# Line_follower1_Sheet.net
KiCad netlist of a schematic drawn in Altium Designer
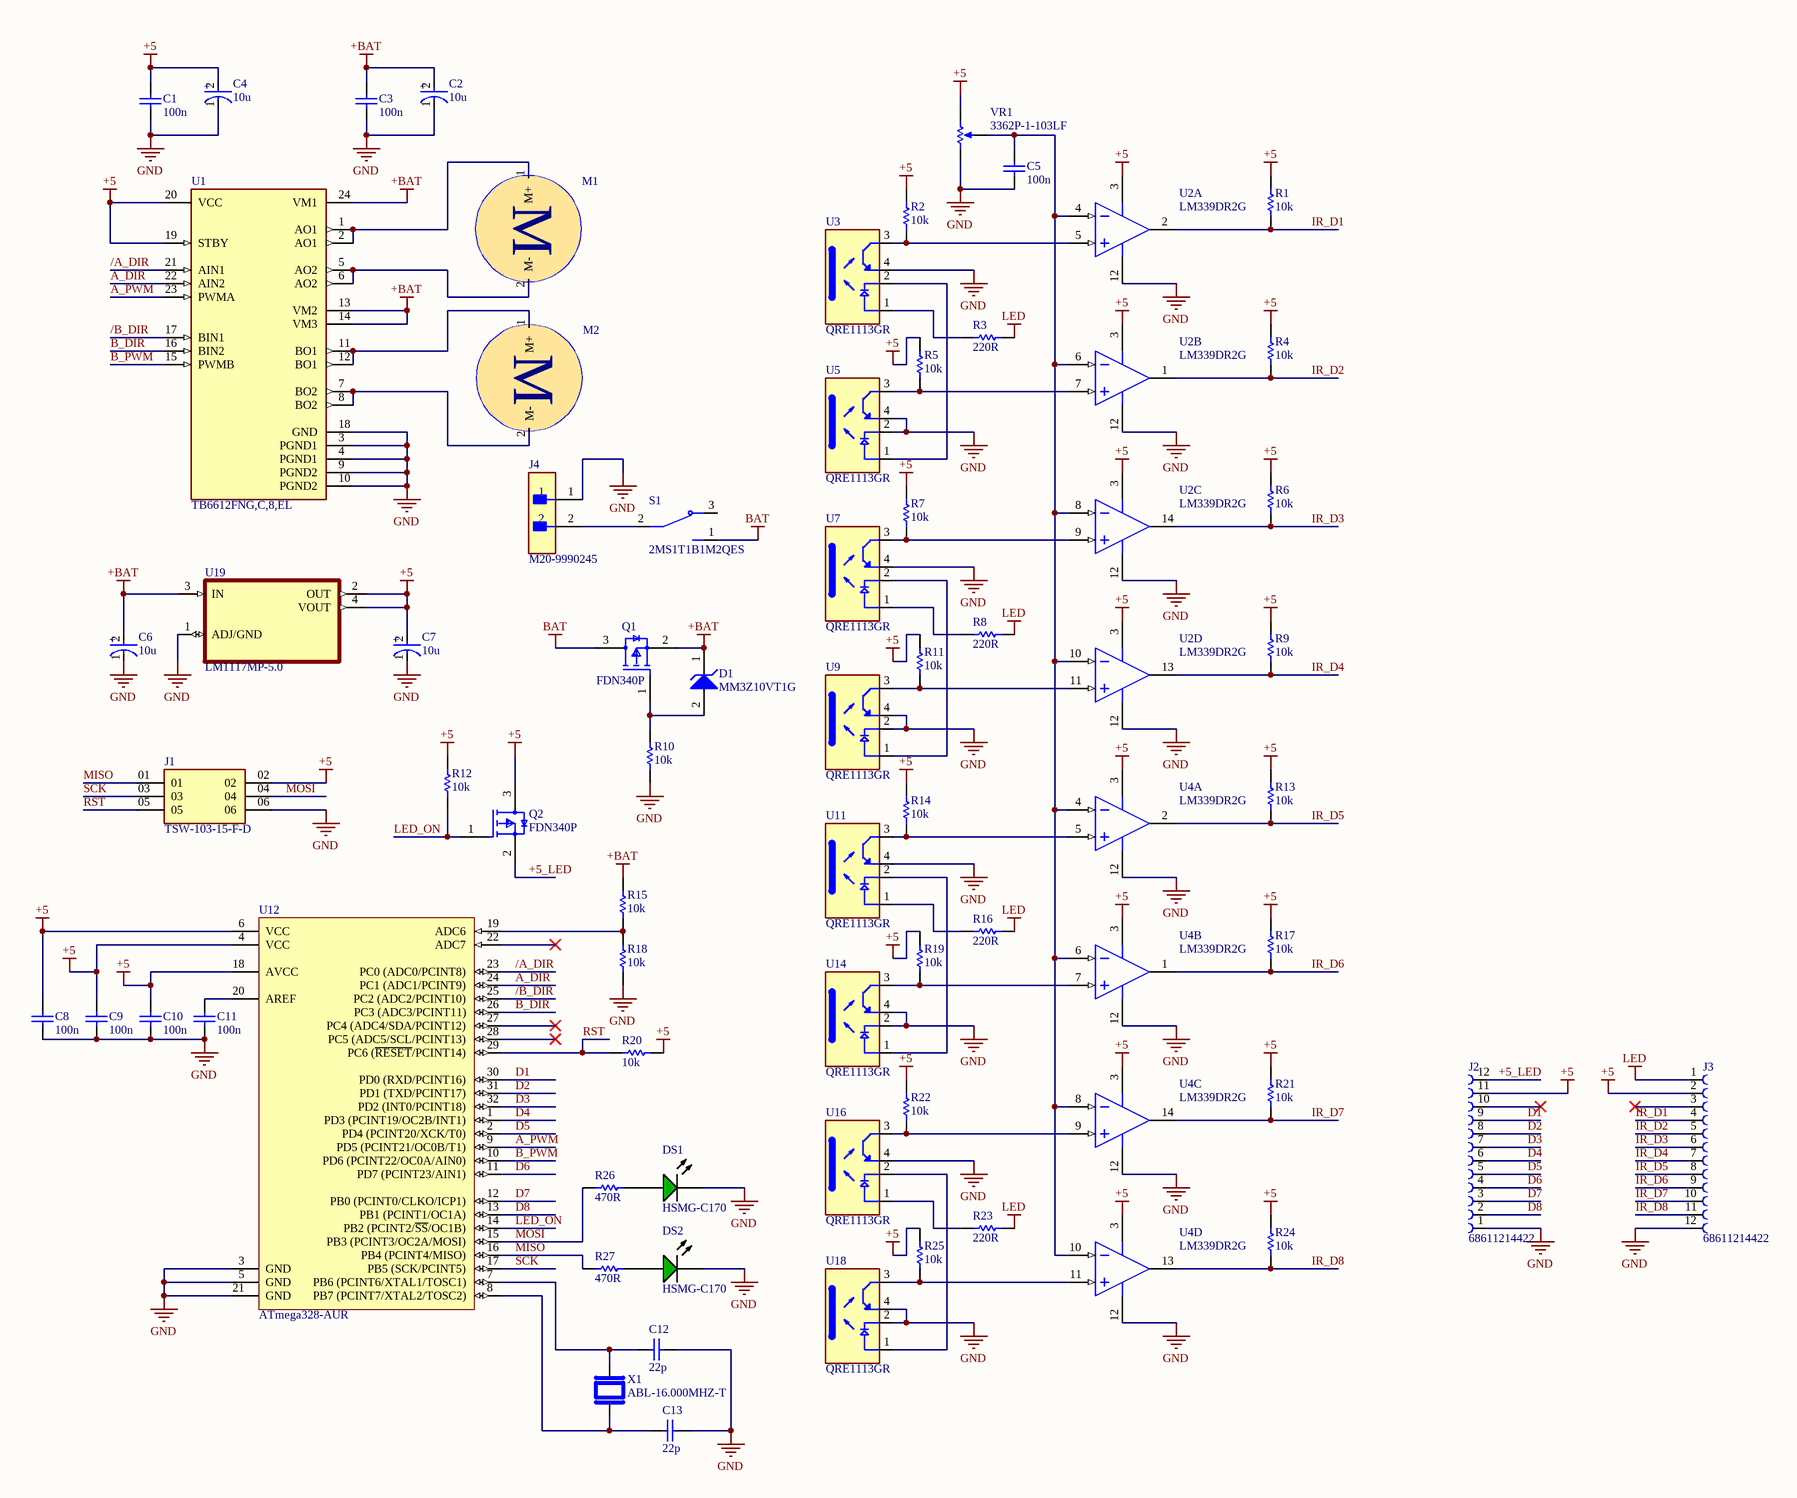
[diagram p0: Line_follower1_Sheet.SchDoc]

(export (version "E")
  (design (tool "Eeschema 10.0.6"))
  (components
    (comp (ref "C1")
      (value "100n")
      (footprint "CAPC2013X88X50LL20T25")
      (description "0805")
      (fields (field (name "MANUFACTURER") "Kemet") (field (name "PART NUMBER") "C0805C103K5RACTU"))
      (libsource (lib "Altium Content Vault") (part "CAP"))
    )
    (comp (ref "C2")
      (value "10u")
      (footprint "FP-T491B106K020AT-MFG")
      (description "CAP TANT 10UF 10% 20V 1411")
      (fields (field (name "TOLERANCE") "10%") (field (name "VOLTAGE") "20V"))
      (libsource (lib "Altium Content Vault") (part "a00bbbee19879c290e62620ae7e47b1"))
    )
    (comp (ref "C3")
      (value "100n")
      (footprint "CAPC2013X88X50LL20T25")
      (description "0805")
      (fields (field (name "MANUFACTURER") "Kemet") (field (name "PART NUMBER") "C0805C103K5RACTU"))
      (libsource (lib "Altium Content Vault") (part "CAP"))
    )
    (comp (ref "C4")
      (value "10u")
      (footprint "FP-T491B106K020AT-MFG")
      (description "CAP TANT 10UF 10% 20V 1411")
      (fields (field (name "TOLERANCE") "10%") (field (name "VOLTAGE") "20V"))
      (libsource (lib "Altium Content Vault") (part "a00bbbee19879c290e62620ae7e47b1"))
    )
    (comp (ref "C5")
      (value "100n")
      (footprint "CAPC2013X88X50LL20T25")
      (description "0805")
      (fields (field (name "MANUFACTURER") "Kemet") (field (name "PART NUMBER") "C0805C103K5RACTU"))
      (libsource (lib "Altium Content Vault") (part "CAP"))
    )
    (comp (ref "C6")
      (value "10u")
      (footprint "FP-T491B106K020AT-MFG")
      (description "CAP TANT 10UF 10% 20V 1411")
      (fields (field (name "TOLERANCE") "10%") (field (name "VOLTAGE") "20V"))
      (libsource (lib "Altium Content Vault") (part "a00bbbee19879c290e62620ae7e47b1"))
    )
    (comp (ref "C7")
      (value "10u")
      (footprint "FP-T491B106K020AT-MFG")
      (description "CAP TANT 10UF 10% 20V 1411")
      (fields (field (name "TOLERANCE") "10%") (field (name "VOLTAGE") "20V"))
      (libsource (lib "Altium Content Vault") (part "a00bbbee19879c290e62620ae7e47b1"))
    )
    (comp (ref "C8")
      (value "100n")
      (footprint "CAPC2013X88X50LL20T25")
      (description "0805")
      (fields (field (name "MANUFACTURER") "Kemet") (field (name "PART NUMBER") "C0805C103K5RACTU"))
      (libsource (lib "Altium Content Vault") (part "CAP"))
    )
    (comp (ref "C9")
      (value "100n")
      (footprint "CAPC2013X88X50LL20T25")
      (description "0805")
      (fields (field (name "MANUFACTURER") "Kemet") (field (name "PART NUMBER") "C0805C103K5RACTU"))
      (libsource (lib "Altium Content Vault") (part "CAP"))
    )
    (comp (ref "C10")
      (value "100n")
      (footprint "CAPC2013X88X50LL20T25")
      (description "0805")
      (fields (field (name "MANUFACTURER") "Kemet") (field (name "PART NUMBER") "C0805C103K5RACTU"))
      (libsource (lib "Altium Content Vault") (part "CAP"))
    )
    (comp (ref "C11")
      (value "100n")
      (footprint "CAPC2013X88X50LL20T25")
      (description "0805")
      (fields (field (name "MANUFACTURER") "Kemet") (field (name "PART NUMBER") "C0805C103K5RACTU"))
      (libsource (lib "Altium Content Vault") (part "CAP"))
    )
    (comp (ref "C12")
      (value "22p")
      (footprint "CAPC2013X88X50LL20T25")
      (description "0805")
      (fields (field (name "MANUFACTURER") "Kemet") (field (name "PART NUMBER") "C0805C103K5RACTU"))
      (libsource (lib "Altium Content Vault") (part "CAP"))
    )
    (comp (ref "C13")
      (value "22p")
      (footprint "CAPC2013X88X50LL20T25")
      (description "0805")
      (fields (field (name "MANUFACTURER") "Kemet") (field (name "PART NUMBER") "C0805C103K5RACTU"))
      (libsource (lib "Altium Content Vault") (part "CAP"))
    )
    (comp (ref "D1")
      (value "MM3Z10VT1G")
      (footprint "ONSC-SOD-323-2-477-02_V")
      (description "Zener Voltage Regulator, 300 mW, 2-Pin SOD-323, Pb-Free, Tape and Reel")
      (fields (field (name "MANUFACTURER") "On Semiconductor"))
      (libsource (lib "Altium Content Vault") (part "ONSC-K1A2-2"))
    )
    (comp (ref "DS1")
      (value "HSMG-C170")
      (footprint "AVAG-HSMX-C170_V")
      (description "Chip LED, Green, 2.2 V, -40 to 85 degC, 2-Pin SMD, Pb-Free, Tape and Reel")
      (fields (field (name "MANUFACTURER") "Avago"))
      (libsource (lib "Altium Content Vault") (part "LED_GREEN_A1K2-2"))
    )
    (comp (ref "DS2")
      (value "HSMG-C170")
      (footprint "AVAG-HSMX-C170_V")
      (description "Chip LED, Green, 2.2 V, -40 to 85 degC, 2-Pin SMD, Pb-Free, Tape and Reel")
      (fields (field (name "MANUFACTURER") "Avago"))
      (libsource (lib "Altium Content Vault") (part "LED_GREEN_A1K2-2"))
    )
    (comp (ref "J1")
      (value "TSW-103-15-F-D")
      (footprint "SAMTEC_TSW-103-15-F-D")
      (libsource (lib "TSW-103-15-F-D") (part "TSW-103-15-F-D"))
    )
    (comp (ref "J2")
      (value "68611214422")
      (footprint "68611214422")
      (description "12 Position FPC Connector Contacts, Bottom 0.039 (1.00mm) Surface Mount, Right Angle")
      (fields (field (name "MF") "Wurth Elektronik"))
      (libsource (lib "68611214422") (part "68611214422"))
    )
    (comp (ref "J3")
      (value "68611214422")
      (footprint "68611214422")
      (description "12 Position FPC Connector Contacts, Bottom 0.039 (1.00mm) Surface Mount, Right Angle")
      (fields (field (name "MF") "Wurth Elektronik"))
      (libsource (lib "68611214422") (part "68611214422"))
    )
    (comp (ref "J4")
      (value "M20-9990245")
      (footprint "FP-M20-9990245-MFG")
      (description "CONN HEADER VERT 2POS 2.54MM")
      (fields (field (name "VOLTAGE") "50V"))
      (libsource (lib "Altium Content Vault") (part "3bc925449376181038e59eaffc5286c"))
    )
    (comp (ref "M1")
      (value "Component_1")
      (footprint "PCBComponent_1")
      (description "Pady do silnika")
      (libsource (lib "PadyDoN20") (part "Component_1"))
    )
    (comp (ref "M2")
      (value "Component_1")
      (footprint "PCBComponent_1")
      (description "Pady do silnika")
      (libsource (lib "PadyDoN20") (part "Component_1"))
    )
    (comp (ref "Q1")
      (value "FDN340P")
      (footprint "FP-527AG-MFG")
      (description "MOSFET P-CH 20V 2A SSOT3")
      (libsource (lib "Altium Content Vault") (part "d23f43cc42f60b967b7caccf14518fd"))
    )
    (comp (ref "Q2")
      (value "FDN340P")
      (footprint "FP-527AG-MFG")
      (description "MOSFET P-CH 20V 2A SSOT3")
      (libsource (lib "Altium Content Vault") (part "d23f43cc42f60b967b7caccf14518fd"))
    )
    (comp (ref "R1")
      (value "10k")
      (footprint "RESC0805(2012)_L")
      (description "10K 0.125W 1% 0805 (2012 Metric)  SMD")
      (fields (field (name "TOLERANCE") "1 %") (field (name "POWER") "0.125 W"))
      (libsource (lib "Altium Content Vault") (part "RES"))
    )
    (comp (ref "R2")
      (value "10k")
      (footprint "RESC0805(2012)_L")
      (description "10K 0.125W 1% 0805 (2012 Metric)  SMD")
      (fields (field (name "TOLERANCE") "1 %") (field (name "POWER") "0.125 W"))
      (libsource (lib "Altium Content Vault") (part "RES"))
    )
    (comp (ref "R3")
      (value "220R")
      (footprint "RESC0805(2012)_L")
      (description "220 0.125W 1% 0805 (2012 Metric)  SMD")
      (fields (field (name "TOLERANCE") "1 %") (field (name "POWER") "0.125 W"))
      (libsource (lib "Altium Content Vault") (part "RES"))
    )
    (comp (ref "R4")
      (value "10k")
      (footprint "RESC0805(2012)_L")
      (description "10K 0.125W 1% 0805 (2012 Metric)  SMD")
      (fields (field (name "TOLERANCE") "1 %") (field (name "POWER") "0.125 W"))
      (libsource (lib "Altium Content Vault") (part "RES"))
    )
    (comp (ref "R5")
      (value "10k")
      (footprint "RESC0805(2012)_L")
      (description "10K 0.125W 1% 0805 (2012 Metric)  SMD")
      (fields (field (name "TOLERANCE") "1 %") (field (name "POWER") "0.125 W"))
      (libsource (lib "Altium Content Vault") (part "RES"))
    )
    (comp (ref "R6")
      (value "10k")
      (footprint "RESC0805(2012)_L")
      (description "10K 0.125W 1% 0805 (2012 Metric)  SMD")
      (fields (field (name "TOLERANCE") "1 %") (field (name "POWER") "0.125 W"))
      (libsource (lib "Altium Content Vault") (part "RES"))
    )
    (comp (ref "R7")
      (value "10k")
      (footprint "RESC0805(2012)_L")
      (description "10K 0.125W 1% 0805 (2012 Metric)  SMD")
      (fields (field (name "TOLERANCE") "1 %") (field (name "POWER") "0.125 W"))
      (libsource (lib "Altium Content Vault") (part "RES"))
    )
    (comp (ref "R8")
      (value "220R")
      (footprint "RESC0805(2012)_L")
      (description "220 0.125W 1% 0805 (2012 Metric)  SMD")
      (fields (field (name "TOLERANCE") "1 %") (field (name "POWER") "0.125 W"))
      (libsource (lib "Altium Content Vault") (part "RES"))
    )
    (comp (ref "R9")
      (value "10k")
      (footprint "RESC0805(2012)_L")
      (description "10K 0.125W 1% 0805 (2012 Metric)  SMD")
      (fields (field (name "TOLERANCE") "1 %") (field (name "POWER") "0.125 W"))
      (libsource (lib "Altium Content Vault") (part "RES"))
    )
    (comp (ref "R10")
      (value "10k")
      (footprint "RESC0805(2012)_L")
      (description "10K 0.125W 1% 0805 (2012 Metric)  SMD")
      (fields (field (name "TOLERANCE") "1 %") (field (name "POWER") "0.125 W"))
      (libsource (lib "Altium Content Vault") (part "RES"))
    )
    (comp (ref "R11")
      (value "10k")
      (footprint "RESC0805(2012)_L")
      (description "10K 0.125W 1% 0805 (2012 Metric)  SMD")
      (fields (field (name "TOLERANCE") "1 %") (field (name "POWER") "0.125 W"))
      (libsource (lib "Altium Content Vault") (part "RES"))
    )
    (comp (ref "R12")
      (value "10k")
      (footprint "RESC0805(2012)_L")
      (description "10K 0.125W 1% 0805 (2012 Metric)  SMD")
      (fields (field (name "TOLERANCE") "1 %") (field (name "POWER") "0.125 W"))
      (libsource (lib "Altium Content Vault") (part "RES"))
    )
    (comp (ref "R13")
      (value "10k")
      (footprint "RESC0805(2012)_L")
      (description "10K 0.125W 1% 0805 (2012 Metric)  SMD")
      (fields (field (name "TOLERANCE") "1 %") (field (name "POWER") "0.125 W"))
      (libsource (lib "Altium Content Vault") (part "RES"))
    )
    (comp (ref "R14")
      (value "10k")
      (footprint "RESC0805(2012)_L")
      (description "10K 0.125W 1% 0805 (2012 Metric)  SMD")
      (fields (field (name "TOLERANCE") "1 %") (field (name "POWER") "0.125 W"))
      (libsource (lib "Altium Content Vault") (part "RES"))
    )
    (comp (ref "R15")
      (value "10k")
      (footprint "RESC0805(2012)_L")
      (description "10K 0.125W 1% 0805 (2012 Metric)  SMD")
      (fields (field (name "TOLERANCE") "1 %") (field (name "POWER") "0.125 W"))
      (libsource (lib "Altium Content Vault") (part "RES"))
    )
    (comp (ref "R16")
      (value "220R")
      (footprint "RESC0805(2012)_L")
      (description "220 0.125W 1% 0805 (2012 Metric)  SMD")
      (fields (field (name "TOLERANCE") "1 %") (field (name "POWER") "0.125 W"))
      (libsource (lib "Altium Content Vault") (part "RES"))
    )
    (comp (ref "R17")
      (value "10k")
      (footprint "RESC0805(2012)_L")
      (description "10K 0.125W 1% 0805 (2012 Metric)  SMD")
      (fields (field (name "TOLERANCE") "1 %") (field (name "POWER") "0.125 W"))
      (libsource (lib "Altium Content Vault") (part "RES"))
    )
    (comp (ref "R18")
      (value "10k")
      (footprint "RESC0805(2012)_L")
      (description "10K 0.125W 1% 0805 (2012 Metric)  SMD")
      (fields (field (name "TOLERANCE") "1 %") (field (name "POWER") "0.125 W"))
      (libsource (lib "Altium Content Vault") (part "RES"))
    )
    (comp (ref "R19")
      (value "10k")
      (footprint "RESC0805(2012)_L")
      (description "10K 0.125W 1% 0805 (2012 Metric)  SMD")
      (fields (field (name "TOLERANCE") "1 %") (field (name "POWER") "0.125 W"))
      (libsource (lib "Altium Content Vault") (part "RES"))
    )
    (comp (ref "R20")
      (value "10k")
      (footprint "RESC0805(2012)_L")
      (description "10K 0.125W 1% 0805 (2012 Metric)  SMD")
      (fields (field (name "TOLERANCE") "1 %") (field (name "POWER") "0.125 W"))
      (libsource (lib "Altium Content Vault") (part "RES"))
    )
    (comp (ref "R21")
      (value "10k")
      (footprint "RESC0805(2012)_L")
      (description "10K 0.125W 1% 0805 (2012 Metric)  SMD")
      (fields (field (name "TOLERANCE") "1 %") (field (name "POWER") "0.125 W"))
      (libsource (lib "Altium Content Vault") (part "RES"))
    )
    (comp (ref "R22")
      (value "10k")
      (footprint "RESC0805(2012)_L")
      (description "10K 0.125W 1% 0805 (2012 Metric)  SMD")
      (fields (field (name "TOLERANCE") "1 %") (field (name "POWER") "0.125 W"))
      (libsource (lib "Altium Content Vault") (part "RES"))
    )
    (comp (ref "R23")
      (value "220R")
      (footprint "RESC0805(2012)_L")
      (description "220 0.125W 1% 0805 (2012 Metric)  SMD")
      (fields (field (name "TOLERANCE") "1 %") (field (name "POWER") "0.125 W"))
      (libsource (lib "Altium Content Vault") (part "RES"))
    )
    (comp (ref "R24")
      (value "10k")
      (footprint "RESC0805(2012)_L")
      (description "10K 0.125W 1% 0805 (2012 Metric)  SMD")
      (fields (field (name "TOLERANCE") "1 %") (field (name "POWER") "0.125 W"))
      (libsource (lib "Altium Content Vault") (part "RES"))
    )
    (comp (ref "R25")
      (value "10k")
      (footprint "RESC0805(2012)_L")
      (description "10K 0.125W 1% 0805 (2012 Metric)  SMD")
      (fields (field (name "TOLERANCE") "1 %") (field (name "POWER") "0.125 W"))
      (libsource (lib "Altium Content Vault") (part "RES"))
    )
    (comp (ref "R26")
      (value "470R")
      (footprint "RESC0805(2012)_L")
      (description "220 0.125W 1% 0805 (2012 Metric)  SMD")
      (fields (field (name "TOLERANCE") "1 %") (field (name "POWER") "0.125 W"))
      (libsource (lib "Altium Content Vault") (part "RES"))
    )
    (comp (ref "R27")
      (value "470R")
      (footprint "RESC0805(2012)_L")
      (description "220 0.125W 1% 0805 (2012 Metric)  SMD")
      (fields (field (name "TOLERANCE") "1 %") (field (name "POWER") "0.125 W"))
      (libsource (lib "Altium Content Vault") (part "RES"))
    )
    (comp (ref "S1")
      (value "2MS1T1B1M2QES")
      (footprint "SW_2MS1T1B1M2QES")
      (description "Toggle Switches Sub-Miniature SPDT switch on-on pc thru-hole")
      (fields (field (name "MF") "Dailywell"))
      (libsource (lib "2MS1T1B1M2QES") (part "2MS1T1B1M2QES"))
    )
    (comp (ref "U1")
      (value "TB6612FNG,C,8,EL")
      (footprint "FP-SSOP24-P-300-0_65A-IPC_A")
      (description "IC MOTOR DRIVER 2.7V-5.5V 24SSOP")
      (libsource (lib "Altium Content Vault") (part "0e8a2fe7f3780dc9c50f4d41012bdec"))
    )
    (comp (ref "U2")
      (value "LM339DR2G")
      (footprint "ONSC-SOIC-14-751A-03_V")
      (description "Single Supply Quad Comparators, 0 to 70 degC, 14-Pin SOIC, Pb-Free, Tape and Reel")
      (fields (field (name "MANUFACTURER") "On Semiconductor"))
      (libsource (lib "Altium Content Vault") (part "ONSC-LM239_LM339_LM2901_NCV2901_MC3302_LMV339-14"))
    )
    (comp (ref "U3")
      (value "QRE1113GR")
      (footprint "SOIC180P460X187-4N")
      (description "Reflective Optical Sensor 0.039 (1mm) 4-SMD, Gull Wing")
      (fields (field (name "MF") "ON Semiconductor"))
      (libsource (lib "QRE1113GR") (part "QRE1113GR"))
    )
    (comp (ref "U4")
      (value "LM339DR2G")
      (footprint "ONSC-SOIC-14-751A-03_V")
      (description "Single Supply Quad Comparators, 0 to 70 degC, 14-Pin SOIC, Pb-Free, Tape and Reel")
      (fields (field (name "MANUFACTURER") "On Semiconductor"))
      (libsource (lib "Altium Content Vault") (part "ONSC-LM239_LM339_LM2901_NCV2901_MC3302_LMV339-14"))
    )
    (comp (ref "U5")
      (value "QRE1113GR")
      (footprint "SOIC180P460X187-4N")
      (description "Reflective Optical Sensor 0.039 (1mm) 4-SMD, Gull Wing")
      (fields (field (name "MF") "ON Semiconductor"))
      (libsource (lib "QRE1113GR") (part "QRE1113GR"))
    )
    (comp (ref "U7")
      (value "QRE1113GR")
      (footprint "SOIC180P460X187-4N")
      (description "Reflective Optical Sensor 0.039 (1mm) 4-SMD, Gull Wing")
      (fields (field (name "MF") "ON Semiconductor"))
      (libsource (lib "QRE1113GR") (part "QRE1113GR"))
    )
    (comp (ref "U9")
      (value "QRE1113GR")
      (footprint "SOIC180P460X187-4N")
      (description "Reflective Optical Sensor 0.039 (1mm) 4-SMD, Gull Wing")
      (fields (field (name "MF") "ON Semiconductor"))
      (libsource (lib "QRE1113GR") (part "QRE1113GR"))
    )
    (comp (ref "U11")
      (value "QRE1113GR")
      (footprint "SOIC180P460X187-4N")
      (description "Reflective Optical Sensor 0.039 (1mm) 4-SMD, Gull Wing")
      (fields (field (name "MF") "ON Semiconductor"))
      (libsource (lib "QRE1113GR") (part "QRE1113GR"))
    )
    (comp (ref "U12")
      (value "ATmega328-AUR")
      (footprint "32A_L")
      (libsource (lib "Altium Content Vault") (part "MC-8B-ATM48-SQ32"))
    )
    (comp (ref "U14")
      (value "QRE1113GR")
      (footprint "SOIC180P460X187-4N")
      (description "Reflective Optical Sensor 0.039 (1mm) 4-SMD, Gull Wing")
      (fields (field (name "MF") "ON Semiconductor"))
      (libsource (lib "QRE1113GR") (part "QRE1113GR"))
    )
    (comp (ref "U16")
      (value "QRE1113GR")
      (footprint "SOIC180P460X187-4N")
      (description "Reflective Optical Sensor 0.039 (1mm) 4-SMD, Gull Wing")
      (fields (field (name "MF") "ON Semiconductor"))
      (libsource (lib "QRE1113GR") (part "QRE1113GR"))
    )
    (comp (ref "U18")
      (value "QRE1113GR")
      (footprint "SOIC180P460X187-4N")
      (description "Reflective Optical Sensor 0.039 (1mm) 4-SMD, Gull Wing")
      (fields (field (name "MF") "ON Semiconductor"))
      (libsource (lib "QRE1113GR") (part "QRE1113GR"))
    )
    (comp (ref "U19")
      (value "LM1117MP-5.0")
      (footprint "SOT230P700X180-4N")
      (description "Space Saving 800mA Low-Dropout Linear Regulator with Internal Current Limit")
      (fields (field (name "MF") "Texas Instruments") (field (name "MP") "LM1117MP-5.0/NOPB"))
      (libsource (lib "LM1117MP-5.0") (part "LM1117MP-5.0"))
    )
    (comp (ref "VR1")
      (value "3362P-1-103LF")
      (footprint "BOUR-3362P")
      (description "Square Trimpot(R) Trimming Potentiometer, 10 KOhm, 300 V, -55 to 125 degC, 3-Pin THD, RoHS, Tube")
      (fields (field (name "TOLERANCE") "1%"))
      (libsource (lib "Altium Content Vault") (part "RES-POT-3"))
    )
    (comp (ref "X1")
      (value "ABL-16.000MHZ-T")
      (footprint "XTAL_HC49P488W46L1150T500H350")
      (description "16 MHz Â±10ppm Crystal 18pF 40 Ohms HC-49/US")
      (fields (field (name "MF") "Abracon Corporation") (field (name "MP") "ABL-16.000MHZ"))
      (libsource (lib "ABL-16.000MHZ-T") (part "ABL-16.000MHZ-T"))
    )
  )
  (nets
    (net (code "1") (name "+5") (class "Default")
      (node (ref "C1") (pin "2") (pinfunction "2_2") (pintype "passive"))
      (node (ref "C10") (pin "2") (pinfunction "2_2") (pintype "passive"))
      (node (ref "C4") (pin "2") (pinfunction "A_2") (pintype "passive"))
      (node (ref "C7") (pin "2") (pinfunction "A_2") (pintype "passive"))
      (node (ref "C8") (pin "2") (pinfunction "2_2") (pintype "passive"))
      (node (ref "C9") (pin "2") (pinfunction "2_2") (pintype "passive"))
      (node (ref "J1") (pin "02") (pinfunction "02_02") (pintype "passive"))
      (node (ref "J2") (pin "11") (pinfunction "2_11") (pintype "passive"))
      (node (ref "J3") (pin "2") (pinfunction "11_2") (pintype "passive"))
      (node (ref "Q2") (pin "3") (pinfunction "D_3") (pintype "passive"))
      (node (ref "R1") (pin "2") (pinfunction "2_2") (pintype "passive"))
      (node (ref "R11") (pin "2") (pinfunction "2_2") (pintype "passive"))
      (node (ref "R12") (pin "2") (pinfunction "2_2") (pintype "passive"))
      (node (ref "R13") (pin "2") (pinfunction "2_2") (pintype "passive"))
      (node (ref "R14") (pin "2") (pinfunction "2_2") (pintype "passive"))
      (node (ref "R17") (pin "2") (pinfunction "2_2") (pintype "passive"))
      (node (ref "R19") (pin "2") (pinfunction "2_2") (pintype "passive"))
      (node (ref "R2") (pin "2") (pinfunction "2_2") (pintype "passive"))
      (node (ref "R20") (pin "1") (pinfunction "1_1") (pintype "passive"))
      (node (ref "R21") (pin "2") (pinfunction "2_2") (pintype "passive"))
      (node (ref "R22") (pin "2") (pinfunction "2_2") (pintype "passive"))
      (node (ref "R24") (pin "2") (pinfunction "2_2") (pintype "passive"))
      (node (ref "R25") (pin "2") (pinfunction "2_2") (pintype "passive"))
      (node (ref "R4") (pin "2") (pinfunction "2_2") (pintype "passive"))
      (node (ref "R5") (pin "2") (pinfunction "2_2") (pintype "passive"))
      (node (ref "R6") (pin "2") (pinfunction "2_2") (pintype "passive"))
      (node (ref "R7") (pin "2") (pinfunction "2_2") (pintype "passive"))
      (node (ref "R9") (pin "2") (pinfunction "2_2") (pintype "passive"))
      (node (ref "U1") (pin "19") (pinfunction "STBY_19") (pintype "input"))
      (node (ref "U1") (pin "20") (pinfunction "VCC_20") (pintype "power_in"))
      (node (ref "U12") (pin "18") (pinfunction "AVCC_18") (pintype "power_in"))
      (node (ref "U12") (pin "4") (pinfunction "VCC_4") (pintype "power_in"))
      (node (ref "U12") (pin "6") (pinfunction "VCC_6") (pintype "power_in"))
      (node (ref "U19") (pin "2") (pinfunction "OUT_2") (pintype "output"))
      (node (ref "U19") (pin "4") (pinfunction "VOUT_4") (pintype "output"))
      (node (ref "U2") (pin "3") (pinfunction "VCC_3") (pintype "power_in"))
      (node (ref "U4") (pin "3") (pinfunction "VCC_3") (pintype "power_in"))
      (node (ref "VR1") (pin "3") (pinfunction "CW_3") (pintype "passive"))
    )
    (net (code "2") (name "+BAT") (class "Default")
      (node (ref "C2") (pin "2") (pinfunction "A_2") (pintype "passive"))
      (node (ref "C3") (pin "2") (pinfunction "2_2") (pintype "passive"))
      (node (ref "C6") (pin "2") (pinfunction "A_2") (pintype "passive"))
      (node (ref "D1") (pin "1") (pinfunction "K_1") (pintype "passive"))
      (node (ref "Q1") (pin "2") (pinfunction "S_2") (pintype "passive"))
      (node (ref "R15") (pin "2") (pinfunction "2_2") (pintype "passive"))
      (node (ref "U1") (pin "13") (pinfunction "VM2_13") (pintype "power_in"))
      (node (ref "U1") (pin "14") (pinfunction "VM3_14") (pintype "power_in"))
      (node (ref "U1") (pin "24") (pinfunction "VM1_24") (pintype "power_in"))
      (node (ref "U19") (pin "3") (pinfunction "IN_3") (pintype "input"))
    )
    (net (code "3") (name "/+5_LED") (class "Default")
      (node (ref "J2") (pin "12") (pinfunction "1_12") (pintype "passive"))
      (node (ref "Q2") (pin "2") (pinfunction "S_2") (pintype "passive"))
    )
    (net (code "4") (name "/A_DIR") (class "Default")
      (node (ref "U1") (pin "22") (pinfunction "AIN2_22") (pintype "input"))
      (node (ref "U12") (pin "24") (pinfunction "PC1_(ADC1/PCINT9)_24") (pintype "bidirectional"))
    )
    (net (code "5") (name "/A_PWM") (class "Default")
      (node (ref "U1") (pin "23") (pinfunction "PWMA_23") (pintype "input"))
      (node (ref "U12") (pin "9") (pinfunction "PD5_(PCINT21/OC0B/T1)_9") (pintype "bidirectional"))
    )
    (net (code "6") (name "/B_DIR") (class "Default")
      (node (ref "U1") (pin "16") (pinfunction "BIN2_16") (pintype "input"))
      (node (ref "U12") (pin "26") (pinfunction "PC3_(ADC3/PCINT11)_26") (pintype "bidirectional"))
    )
    (net (code "7") (name "/B_PWM") (class "Default")
      (node (ref "U1") (pin "15") (pinfunction "PWMB_15") (pintype "input"))
      (node (ref "U12") (pin "10") (pinfunction "PD6_(PCINT22/OC0A/AIN0)_10") (pintype "bidirectional"))
    )
    (net (code "8") (name "/D1") (class "Default")
      (node (ref "J2") (pin "9") (pinfunction "4_9") (pintype "passive"))
      (node (ref "U12") (pin "30") (pinfunction "PD0_(RXD/PCINT16)_30") (pintype "bidirectional"))
    )
    (net (code "9") (name "/D2") (class "Default")
      (node (ref "J2") (pin "8") (pinfunction "5_8") (pintype "passive"))
      (node (ref "U12") (pin "31") (pinfunction "PD1_(TXD/PCINT17)_31") (pintype "bidirectional"))
    )
    (net (code "10") (name "/D3") (class "Default")
      (node (ref "J2") (pin "7") (pinfunction "6_7") (pintype "passive"))
      (node (ref "U12") (pin "32") (pinfunction "PD2_(INT0/PCINT18)_32") (pintype "bidirectional"))
    )
    (net (code "11") (name "/D4") (class "Default")
      (node (ref "J2") (pin "6") (pinfunction "7_6") (pintype "passive"))
      (node (ref "U12") (pin "1") (pinfunction "PD3_(PCINT19/OC2B/INT1)_1") (pintype "bidirectional"))
    )
    (net (code "12") (name "/D5") (class "Default")
      (node (ref "J2") (pin "5") (pinfunction "8_5") (pintype "passive"))
      (node (ref "U12") (pin "2") (pinfunction "PD4_(PCINT20/XCK/T0)_2") (pintype "bidirectional"))
    )
    (net (code "13") (name "/D6") (class "Default")
      (node (ref "J2") (pin "4") (pinfunction "9_4") (pintype "passive"))
      (node (ref "U12") (pin "11") (pinfunction "PD7_(PCINT23/AIN1)_11") (pintype "bidirectional"))
    )
    (net (code "14") (name "/D7") (class "Default")
      (node (ref "J2") (pin "3") (pinfunction "10_3") (pintype "passive"))
      (node (ref "U12") (pin "12") (pinfunction "PB0_(PCINT0/CLKO/ICP1)_12") (pintype "bidirectional"))
    )
    (net (code "15") (name "/D8") (class "Default")
      (node (ref "J2") (pin "2") (pinfunction "11_2") (pintype "passive"))
      (node (ref "U12") (pin "13") (pinfunction "PB1_(PCINT1/OC1A)_13") (pintype "bidirectional"))
    )
    (net (code "16") (name "/IR_D1") (class "Default")
      (node (ref "J3") (pin "4") (pinfunction "9_4") (pintype "passive"))
      (node (ref "R1") (pin "1") (pinfunction "1_1") (pintype "passive"))
      (node (ref "U2") (pin "2") (pinfunction "OUT1_2") (pintype "open_collector"))
    )
    (net (code "17") (name "/IR_D2") (class "Default")
      (node (ref "J3") (pin "5") (pinfunction "8_5") (pintype "passive"))
      (node (ref "R4") (pin "1") (pinfunction "1_1") (pintype "passive"))
      (node (ref "U2") (pin "1") (pinfunction "OUT2_1") (pintype "open_collector"))
    )
    (net (code "18") (name "/IR_D3") (class "Default")
      (node (ref "J3") (pin "6") (pinfunction "7_6") (pintype "passive"))
      (node (ref "R6") (pin "1") (pinfunction "1_1") (pintype "passive"))
      (node (ref "U2") (pin "14") (pinfunction "OUT3_14") (pintype "open_collector"))
    )
    (net (code "19") (name "/IR_D4") (class "Default")
      (node (ref "J3") (pin "7") (pinfunction "6_7") (pintype "passive"))
      (node (ref "R9") (pin "1") (pinfunction "1_1") (pintype "passive"))
      (node (ref "U2") (pin "13") (pinfunction "OUT4_13") (pintype "open_collector"))
    )
    (net (code "20") (name "/IR_D5") (class "Default")
      (node (ref "J3") (pin "8") (pinfunction "5_8") (pintype "passive"))
      (node (ref "R13") (pin "1") (pinfunction "1_1") (pintype "passive"))
      (node (ref "U4") (pin "2") (pinfunction "OUT1_2") (pintype "open_collector"))
    )
    (net (code "21") (name "/IR_D6") (class "Default")
      (node (ref "J3") (pin "9") (pinfunction "4_9") (pintype "passive"))
      (node (ref "R17") (pin "1") (pinfunction "1_1") (pintype "passive"))
      (node (ref "U4") (pin "1") (pinfunction "OUT2_1") (pintype "open_collector"))
    )
    (net (code "22") (name "/IR_D7") (class "Default")
      (node (ref "J3") (pin "10") (pinfunction "3_10") (pintype "passive"))
      (node (ref "R21") (pin "1") (pinfunction "1_1") (pintype "passive"))
      (node (ref "U4") (pin "14") (pinfunction "OUT3_14") (pintype "open_collector"))
    )
    (net (code "23") (name "/IR_D8") (class "Default")
      (node (ref "J3") (pin "11") (pinfunction "2_11") (pintype "passive"))
      (node (ref "R24") (pin "1") (pinfunction "1_1") (pintype "passive"))
      (node (ref "U4") (pin "13") (pinfunction "OUT4_13") (pintype "open_collector"))
    )
    (net (code "24") (name "/LED_ON") (class "Default")
      (node (ref "Q2") (pin "1") (pinfunction "G_1") (pintype "passive"))
      (node (ref "R12") (pin "1") (pinfunction "1_1") (pintype "passive"))
      (node (ref "U12") (pin "14") (pinfunction "PB2_(PCINT2/~{SS}/OC1B)_14") (pintype "bidirectional"))
    )
    (net (code "25") (name "/MISO") (class "Default")
      (node (ref "J1") (pin "01") (pinfunction "01_01") (pintype "passive"))
      (node (ref "R27") (pin "2") (pinfunction "2_2") (pintype "passive"))
      (node (ref "U12") (pin "16") (pinfunction "PB4_(PCINT4/MISO)_16") (pintype "bidirectional"))
    )
    (net (code "26") (name "/MOSI") (class "Default")
      (node (ref "J1") (pin "04") (pinfunction "04_04") (pintype "passive"))
      (node (ref "R26") (pin "2") (pinfunction "2_2") (pintype "passive"))
      (node (ref "U12") (pin "15") (pinfunction "PB3_(PCINT3/OC2A/MOSI)_15") (pintype "bidirectional"))
    )
    (net (code "27") (name "/RST") (class "Default")
      (node (ref "J1") (pin "05") (pinfunction "05_05") (pintype "passive"))
      (node (ref "R20") (pin "2") (pinfunction "2_2") (pintype "passive"))
      (node (ref "U12") (pin "29") (pinfunction "PC6_(~{RESET}/PCINT14)_29") (pintype "bidirectional"))
    )
    (net (code "28") (name "/SCK") (class "Default")
      (node (ref "J1") (pin "03") (pinfunction "03_03") (pintype "passive"))
      (node (ref "U12") (pin "17") (pinfunction "PB5_(SCK/PCINT5)_17") (pintype "bidirectional"))
    )
    (net (code "29") (name "/{slash}A_DIR") (class "Default")
      (node (ref "U1") (pin "21") (pinfunction "AIN1_21") (pintype "input"))
      (node (ref "U12") (pin "23") (pinfunction "PC0_(ADC0/PCINT8)_23") (pintype "bidirectional"))
    )
    (net (code "30") (name "/{slash}B_DIR") (class "Default")
      (node (ref "U1") (pin "17") (pinfunction "BIN1_17") (pintype "input"))
      (node (ref "U12") (pin "25") (pinfunction "PC2_(ADC2/PCINT10)_25") (pintype "bidirectional"))
    )
    (net (code "31") (name "BAT") (class "Default")
      (node (ref "Q1") (pin "3") (pinfunction "D_3") (pintype "passive"))
      (node (ref "S1") (pin "1") (pinfunction "1_1") (pintype "passive"))
    )
    (net (code "32") (name "GND") (class "Default")
      (node (ref "C1") (pin "1") (pinfunction "1_1") (pintype "passive"))
      (node (ref "C10") (pin "1") (pinfunction "1_1") (pintype "passive"))
      (node (ref "C11") (pin "1") (pinfunction "1_1") (pintype "passive"))
      (node (ref "C12") (pin "2") (pinfunction "2_2") (pintype "passive"))
      (node (ref "C13") (pin "2") (pinfunction "2_2") (pintype "passive"))
      (node (ref "C2") (pin "1") (pinfunction "C_1") (pintype "passive"))
      (node (ref "C3") (pin "1") (pinfunction "1_1") (pintype "passive"))
      (node (ref "C4") (pin "1") (pinfunction "C_1") (pintype "passive"))
      (node (ref "C5") (pin "1") (pinfunction "1_1") (pintype "passive"))
      (node (ref "C6") (pin "1") (pinfunction "C_1") (pintype "passive"))
      (node (ref "C7") (pin "1") (pinfunction "C_1") (pintype "passive"))
      (node (ref "C8") (pin "1") (pinfunction "1_1") (pintype "passive"))
      (node (ref "C9") (pin "1") (pinfunction "1_1") (pintype "passive"))
      (node (ref "DS1") (pin "2") (pinfunction "K_2") (pintype "passive"))
      (node (ref "DS2") (pin "2") (pinfunction "K_2") (pintype "passive"))
      (node (ref "J1") (pin "06") (pinfunction "06_06") (pintype "passive"))
      (node (ref "J2") (pin "1") (pinfunction "12_1") (pintype "passive"))
      (node (ref "J3") (pin "12") (pinfunction "1_12") (pintype "passive"))
      (node (ref "J4") (pin "1") (pinfunction "1_1") (pintype "passive"))
      (node (ref "R10") (pin "1") (pinfunction "1_1") (pintype "passive"))
      (node (ref "R18") (pin "1") (pinfunction "1_1") (pintype "passive"))
      (node (ref "U1") (pin "10") (pinfunction "PGND2_10") (pintype "power_in"))
      (node (ref "U1") (pin "18") (pinfunction "GND_18") (pintype "power_in"))
      (node (ref "U1") (pin "3") (pinfunction "PGND1_3") (pintype "power_in"))
      (node (ref "U1") (pin "4") (pinfunction "PGND1_4") (pintype "power_in"))
      (node (ref "U1") (pin "9") (pinfunction "PGND2_9") (pintype "power_in"))
      (node (ref "U11") (pin "4") (pinfunction "ET_4") (pintype "passive"))
      (node (ref "U12") (pin "21") (pinfunction "GND_21") (pintype "power_in"))
      (node (ref "U12") (pin "3") (pinfunction "GND_3") (pintype "power_in"))
      (node (ref "U12") (pin "5") (pinfunction "GND_5") (pintype "power_in"))
      (node (ref "U14") (pin "2") (pinfunction "C_2") (pintype "passive"))
      (node (ref "U14") (pin "4") (pinfunction "ET_4") (pintype "passive"))
      (node (ref "U16") (pin "4") (pinfunction "ET_4") (pintype "passive"))
      (node (ref "U18") (pin "2") (pinfunction "C_2") (pintype "passive"))
      (node (ref "U18") (pin "4") (pinfunction "ET_4") (pintype "passive"))
      (node (ref "U19") (pin "1") (pinfunction "ADJ/GND_1") (pintype "bidirectional"))
      (node (ref "U2") (pin "12") (pinfunction "GND_12") (pintype "power_in"))
      (node (ref "U3") (pin "4") (pinfunction "ET_4") (pintype "passive"))
      (node (ref "U4") (pin "12") (pinfunction "GND_12") (pintype "power_in"))
      (node (ref "U5") (pin "2") (pinfunction "C_2") (pintype "passive"))
      (node (ref "U5") (pin "4") (pinfunction "ET_4") (pintype "passive"))
      (node (ref "U7") (pin "4") (pinfunction "ET_4") (pintype "passive"))
      (node (ref "U9") (pin "2") (pinfunction "C_2") (pintype "passive"))
      (node (ref "U9") (pin "4") (pinfunction "ET_4") (pintype "passive"))
      (node (ref "VR1") (pin "1") (pinfunction "CCW_1") (pintype "passive"))
    )
    (net (code "33") (name "LED") (class "Default")
      (node (ref "J3") (pin "1") (pinfunction "12_1") (pintype "passive"))
      (node (ref "R16") (pin "1") (pinfunction "1_1") (pintype "passive"))
      (node (ref "R23") (pin "1") (pinfunction "1_1") (pintype "passive"))
      (node (ref "R3") (pin "1") (pinfunction "1_1") (pintype "passive"))
      (node (ref "R8") (pin "1") (pinfunction "1_1") (pintype "passive"))
    )
    (net (code "34") (name "Net-(D1-A)") (class "Default")
      (node (ref "D1") (pin "2") (pinfunction "A_2") (pintype "passive"))
      (node (ref "Q1") (pin "1") (pinfunction "G_1") (pintype "passive"))
      (node (ref "R10") (pin "2") (pinfunction "2_2") (pintype "passive"))
    )
    (net (code "35") (name "Net-(DS1-A)") (class "Default")
      (node (ref "DS1") (pin "1") (pinfunction "A_1") (pintype "passive"))
      (node (ref "R26") (pin "1") (pinfunction "1_1") (pintype "passive"))
    )
    (net (code "36") (name "Net-(DS2-A)") (class "Default")
      (node (ref "DS2") (pin "1") (pinfunction "A_1") (pintype "passive"))
      (node (ref "R27") (pin "1") (pinfunction "1_1") (pintype "passive"))
    )
    (net (code "37") (name "Net-(J4-Pad2)") (class "Default")
      (node (ref "J4") (pin "2") (pinfunction "2_2") (pintype "passive"))
      (node (ref "S1") (pin "2") (pinfunction "2_2") (pintype "passive"))
    )
    (net (code "38") (name "Net-(M1-M+)") (class "Default")
      (node (ref "M1") (pin "1") (pinfunction "M+_1") (pintype "power_in"))
      (node (ref "U1") (pin "1") (pinfunction "AO1_1") (pintype "output"))
      (node (ref "U1") (pin "2") (pinfunction "AO1_2") (pintype "output"))
    )
    (net (code "39") (name "Net-(M1-M-)") (class "Default")
      (node (ref "M1") (pin "2") (pinfunction "M-_2") (pintype "passive"))
      (node (ref "U1") (pin "5") (pinfunction "AO2_5") (pintype "output"))
      (node (ref "U1") (pin "6") (pinfunction "AO2_6") (pintype "output"))
    )
    (net (code "40") (name "Net-(M2-M+)") (class "Default")
      (node (ref "M2") (pin "1") (pinfunction "M+_1") (pintype "power_in"))
      (node (ref "U1") (pin "11") (pinfunction "BO1_11") (pintype "output"))
      (node (ref "U1") (pin "12") (pinfunction "BO1_12") (pintype "output"))
    )
    (net (code "41") (name "Net-(M2-M-)") (class "Default")
      (node (ref "M2") (pin "2") (pinfunction "M-_2") (pintype "passive"))
      (node (ref "U1") (pin "7") (pinfunction "BO2_7") (pintype "output"))
      (node (ref "U1") (pin "8") (pinfunction "BO2_8") (pintype "output"))
    )
    (net (code "42") (name "Net-(U2A-IN1+)") (class "Default")
      (node (ref "R2") (pin "1") (pinfunction "1_1") (pintype "passive"))
      (node (ref "U2") (pin "5") (pinfunction "IN1+_5") (pintype "input"))
      (node (ref "U3") (pin "3") (pinfunction "CT_3") (pintype "passive"))
    )
    (net (code "43") (name "Net-(U2A-IN1-)") (class "Default")
      (node (ref "C5") (pin "2") (pinfunction "2_2") (pintype "passive"))
      (node (ref "U2") (pin "10") (pinfunction "IN4-_10") (pintype "input"))
      (node (ref "U2") (pin "4") (pinfunction "IN1-_4") (pintype "input"))
      (node (ref "U2") (pin "6") (pinfunction "IN2-_6") (pintype "input"))
      (node (ref "U2") (pin "8") (pinfunction "IN3-_8") (pintype "input"))
      (node (ref "U4") (pin "10") (pinfunction "IN4-_10") (pintype "input"))
      (node (ref "U4") (pin "4") (pinfunction "IN1-_4") (pintype "input"))
      (node (ref "U4") (pin "6") (pinfunction "IN2-_6") (pintype "input"))
      (node (ref "U4") (pin "8") (pinfunction "IN3-_8") (pintype "input"))
      (node (ref "VR1") (pin "2") (pinfunction "S_2") (pintype "passive"))
    )
    (net (code "44") (name "Net-(U2B-IN2+)") (class "Default")
      (node (ref "R5") (pin "1") (pinfunction "1_1") (pintype "passive"))
      (node (ref "U2") (pin "7") (pinfunction "IN2+_7") (pintype "input"))
      (node (ref "U5") (pin "3") (pinfunction "CT_3") (pintype "passive"))
    )
    (net (code "45") (name "Net-(U2C-IN3+)") (class "Default")
      (node (ref "R7") (pin "1") (pinfunction "1_1") (pintype "passive"))
      (node (ref "U2") (pin "9") (pinfunction "IN3+_9") (pintype "input"))
      (node (ref "U7") (pin "3") (pinfunction "CT_3") (pintype "passive"))
    )
    (net (code "46") (name "Net-(U2D-IN4+)") (class "Default")
      (node (ref "R11") (pin "1") (pinfunction "1_1") (pintype "passive"))
      (node (ref "U2") (pin "11") (pinfunction "IN4+_11") (pintype "input"))
      (node (ref "U9") (pin "3") (pinfunction "CT_3") (pintype "passive"))
    )
    (net (code "47") (name "Net-(U3-A)") (class "Default")
      (node (ref "R3") (pin "2") (pinfunction "2_2") (pintype "passive"))
      (node (ref "U3") (pin "1") (pinfunction "A_1") (pintype "passive"))
    )
    (net (code "48") (name "Net-(U3-C)") (class "Default")
      (node (ref "U3") (pin "2") (pinfunction "C_2") (pintype "passive"))
      (node (ref "U5") (pin "1") (pinfunction "A_1") (pintype "passive"))
    )
    (net (code "49") (name "Net-(U7-A)") (class "Default")
      (node (ref "R8") (pin "2") (pinfunction "2_2") (pintype "passive"))
      (node (ref "U7") (pin "1") (pinfunction "A_1") (pintype "passive"))
    )
    (net (code "50") (name "Net-(U7-C)") (class "Default")
      (node (ref "U7") (pin "2") (pinfunction "C_2") (pintype "passive"))
      (node (ref "U9") (pin "1") (pinfunction "A_1") (pintype "passive"))
    )
    (net (code "51") (name "Net-(U11-A)") (class "Default")
      (node (ref "R16") (pin "2") (pinfunction "2_2") (pintype "passive"))
      (node (ref "U11") (pin "1") (pinfunction "A_1") (pintype "passive"))
    )
    (net (code "52") (name "Net-(U11-C)") (class "Default")
      (node (ref "U11") (pin "2") (pinfunction "C_2") (pintype "passive"))
      (node (ref "U14") (pin "1") (pinfunction "A_1") (pintype "passive"))
    )
    (net (code "53") (name "Net-(U11-CT)") (class "Default")
      (node (ref "R14") (pin "1") (pinfunction "1_1") (pintype "passive"))
      (node (ref "U11") (pin "3") (pinfunction "CT_3") (pintype "passive"))
      (node (ref "U4") (pin "5") (pinfunction "IN1+_5") (pintype "input"))
    )
    (net (code "54") (name "Net-(U12-ADC6)") (class "Default")
      (node (ref "R15") (pin "1") (pinfunction "1_1") (pintype "passive"))
      (node (ref "R18") (pin "2") (pinfunction "2_2") (pintype "passive"))
      (node (ref "U12") (pin "19") (pinfunction "ADC6_19") (pintype "input"))
    )
    (net (code "55") (name "Net-(U12-AREF)") (class "Default")
      (node (ref "C11") (pin "2") (pinfunction "2_2") (pintype "passive"))
      (node (ref "U12") (pin "20") (pinfunction "AREF_20") (pintype "passive"))
    )
    (net (code "56") (name "Net-(U12-PB6_(PCINT6{slash}XTAL1{slash}TOSC1))") (class "Default")
      (node (ref "C12") (pin "1") (pinfunction "1_1") (pintype "passive"))
      (node (ref "U12") (pin "7") (pinfunction "PB6_(PCINT6/XTAL1/TOSC1)_7") (pintype "bidirectional"))
      (node (ref "X1") (pin "2") (pinfunction "2_2") (pintype "passive"))
    )
    (net (code "57") (name "Net-(U12-PB7_(PCINT7{slash}XTAL2{slash}TOSC2))") (class "Default")
      (node (ref "C13") (pin "1") (pinfunction "1_1") (pintype "passive"))
      (node (ref "U12") (pin "8") (pinfunction "PB7_(PCINT7/XTAL2/TOSC2)_8") (pintype "bidirectional"))
      (node (ref "X1") (pin "1") (pinfunction "1_1") (pintype "passive"))
    )
    (net (code "58") (name "Net-(U14-CT)") (class "Default")
      (node (ref "R19") (pin "1") (pinfunction "1_1") (pintype "passive"))
      (node (ref "U14") (pin "3") (pinfunction "CT_3") (pintype "passive"))
      (node (ref "U4") (pin "7") (pinfunction "IN2+_7") (pintype "input"))
    )
    (net (code "59") (name "Net-(U16-A)") (class "Default")
      (node (ref "R23") (pin "2") (pinfunction "2_2") (pintype "passive"))
      (node (ref "U16") (pin "1") (pinfunction "A_1") (pintype "passive"))
    )
    (net (code "60") (name "Net-(U16-C)") (class "Default")
      (node (ref "U16") (pin "2") (pinfunction "C_2") (pintype "passive"))
      (node (ref "U18") (pin "1") (pinfunction "A_1") (pintype "passive"))
    )
    (net (code "61") (name "Net-(U16-CT)") (class "Default")
      (node (ref "R22") (pin "1") (pinfunction "1_1") (pintype "passive"))
      (node (ref "U16") (pin "3") (pinfunction "CT_3") (pintype "passive"))
      (node (ref "U4") (pin "9") (pinfunction "IN3+_9") (pintype "input"))
    )
    (net (code "62") (name "Net-(U18-CT)") (class "Default")
      (node (ref "R25") (pin "1") (pinfunction "1_1") (pintype "passive"))
      (node (ref "U18") (pin "3") (pinfunction "CT_3") (pintype "passive"))
      (node (ref "U4") (pin "11") (pinfunction "IN4+_11") (pintype "input"))
    )
    (net (code "63") (name "unconnected-(J2-3-Pad10)") (class "Default")
      (node (ref "J2") (pin "10") (pinfunction "3_10") (pintype "passive+no_connect"))
    )
    (net (code "64") (name "unconnected-(J3-10-Pad3)") (class "Default")
      (node (ref "J3") (pin "3") (pinfunction "10_3") (pintype "passive+no_connect"))
    )
    (net (code "65") (name "unconnected-(S1-Pad3)") (class "Default")
      (node (ref "S1") (pin "3") (pinfunction "3_3") (pintype "passive"))
    )
    (net (code "66") (name "unconnected-(U12-ADC7-Pad22)") (class "Default")
      (node (ref "U12") (pin "22") (pinfunction "ADC7_22") (pintype "input+no_connect"))
    )
    (net (code "67") (name "unconnected-(U12-PC4_(ADC4{slash}SDA{slash}PCINT12)-Pad27)") (class "Default")
      (node (ref "U12") (pin "27") (pinfunction "PC4_(ADC4/SDA/PCINT12)_27") (pintype "bidirectional+no_connect"))
    )
    (net (code "68") (name "unconnected-(U12-PC5_(ADC5{slash}SCL{slash}PCINT13)-Pad28)") (class "Default")
      (node (ref "U12") (pin "28") (pinfunction "PC5_(ADC5/SCL/PCINT13)_28") (pintype "bidirectional+no_connect"))
    )
  )
)
